# 5V_buck.net
KiCad netlist of a schematic drawn in Altium Designer
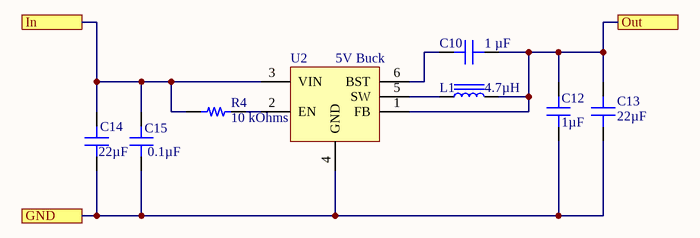
[diagram p0: 5V_buck.SchDoc]

(export (version "E")
  (design (tool "Eeschema 10.0.6"))
  (components
    (comp (ref "C10")
      (value "1 µF")
      (footprint "CAP 0402_1005")
      (description "CAP CER 0.1UF 16V X7R 0402")
      (fields (field (name "PART NUMBER") "C0402C104K4RACAUTO") (field (name "MANUFACTURER") "KEMET"))
      (libsource (lib "Celestial Altium Library - altium_library") (part "Capacitor"))
    )
    (comp (ref "C12")
      (value "1µF")
      (footprint "CAP 0603_1608")
      (description "CAP CER 1UF 25V X7R 0603")
      (fields
        (field (name "PART NUMBER") "GCJ188R71E105KA01D")
        (field (name "MANUFACTURER") "Murata Electronics")
      )
      (libsource (lib "Celestial Altium Library - altium_library") (part "Capacitor"))
    )
    (comp (ref "C13")
      (value "22µF")
      (footprint "CAP 0805_2012")
      (description "CAP CER 22UF 16V X5R 0805")
      (fields
        (field (name "PART NUMBER") "CL21A226MOQNNNE")
        (field (name "MANUFACTURER") "Samsung Electro-Mechanics")
      )
      (libsource (lib "Celestial Altium Library - altium_library") (part "Capacitor"))
    )
    (comp (ref "C14")
      (value "22µF")
      (footprint "CAP 0805_2012")
      (description "CAP CER 10UF 25V X7S 0805")
      (fields
        (field (name "PART NUMBER") "C2012X7S1E106K125AC")
        (field (name "MANUFACTURER") "TDK Corporation")
      )
      (libsource (lib "Celestial Altium Library - altium_library") (part "Capacitor"))
    )
    (comp (ref "C15")
      (value "0.1µF")
      (footprint "CAP 0603_1608")
      (description "CAP CER 0.1UF 100V 0603 EPOXY")
      (fields
        (field (name "PART NUMBER") "GCG188R92A104KA03D")
        (field (name "MANUFACTURER") "Murata Electronics")
      )
      (libsource (lib "Celestial Altium Library - altium_library") (part "Capacitor"))
    )
    (comp (ref "L1")
      (value "4.7µH")
      (footprint "IND 1008_2520")
      (description "FIXED IND 4.7UH 1A 110 MOHM SMD")
      (fields (field (name "PART NUMBER") "MLP2520S4R7ST0S1") (field (name "MANUFACTURER") "TDK Corporation"))
      (libsource (lib "Celestial Altium Library - altium_library") (part "Inductor"))
    )
    (comp (ref "R4")
      (value "10 kOhms")
      (footprint "RES 0402_1005")
      (description "RES 14.3K OHM 1% 1/10W 0402")
      (fields
        (field (name "PART NUMBER") "RK73H1ETTP1432F")
        (field (name "MANUFACTURER") "KOA Speer Electronics, Inc.")
      )
      (libsource (lib "Celestial Altium Library - altium_library") (part "Resistor"))
    )
    (comp (ref "U2")
      (value "5V Buck")
      (footprint "TSOT-26-6 - 3.2mm")
      (description "5V fixed step down Buck")
      (libsource (lib "IC") (part "AP63205WU-7"))
    )
  )
  (nets
    (net (code "1") (name "/GND") (class "Default")
      (node (ref "C12") (pin "1") (pinfunction "1_1") (pintype "passive"))
      (node (ref "C13") (pin "1") (pinfunction "1_1") (pintype "passive"))
      (node (ref "C14") (pin "1") (pinfunction "1_1") (pintype "passive"))
      (node (ref "C15") (pin "2") (pinfunction "2_2") (pintype "passive"))
      (node (ref "U2") (pin "4") (pinfunction "GND_4") (pintype "passive"))
    )
    (net (code "2") (name "/In") (class "Default")
      (node (ref "C14") (pin "2") (pinfunction "2_2") (pintype "passive"))
      (node (ref "C15") (pin "1") (pinfunction "1_1") (pintype "passive"))
      (node (ref "R4") (pin "1") (pinfunction "1_1") (pintype "passive"))
      (node (ref "U2") (pin "3") (pinfunction "VIN_3") (pintype "passive"))
    )
    (net (code "3") (name "/Out") (class "Default")
      (node (ref "C10") (pin "2") (pinfunction "2_2") (pintype "passive"))
      (node (ref "C12") (pin "2") (pinfunction "2_2") (pintype "passive"))
      (node (ref "C13") (pin "2") (pinfunction "2_2") (pintype "passive"))
      (node (ref "L1") (pin "2") (pinfunction "2_2") (pintype "passive"))
      (node (ref "U2") (pin "1") (pinfunction "FB_1") (pintype "passive"))
    )
    (net (code "4") (name "Net-(U2-BST)") (class "Default")
      (node (ref "C10") (pin "1") (pinfunction "1_1") (pintype "passive"))
      (node (ref "U2") (pin "6") (pinfunction "BST_6") (pintype "passive"))
    )
    (net (code "5") (name "Net-(U2-EN)") (class "Default")
      (node (ref "R4") (pin "2") (pinfunction "2_2") (pintype "passive"))
      (node (ref "U2") (pin "2") (pinfunction "EN_2") (pintype "passive"))
    )
    (net (code "6") (name "Net-(U2-SW)") (class "Default")
      (node (ref "L1") (pin "1") (pinfunction "1_1") (pintype "passive"))
      (node (ref "U2") (pin "5") (pinfunction "SW_5") (pintype "passive"))
    )
  )
)
